# P_IN.net
KiCad netlist of a schematic drawn in Altium Designer
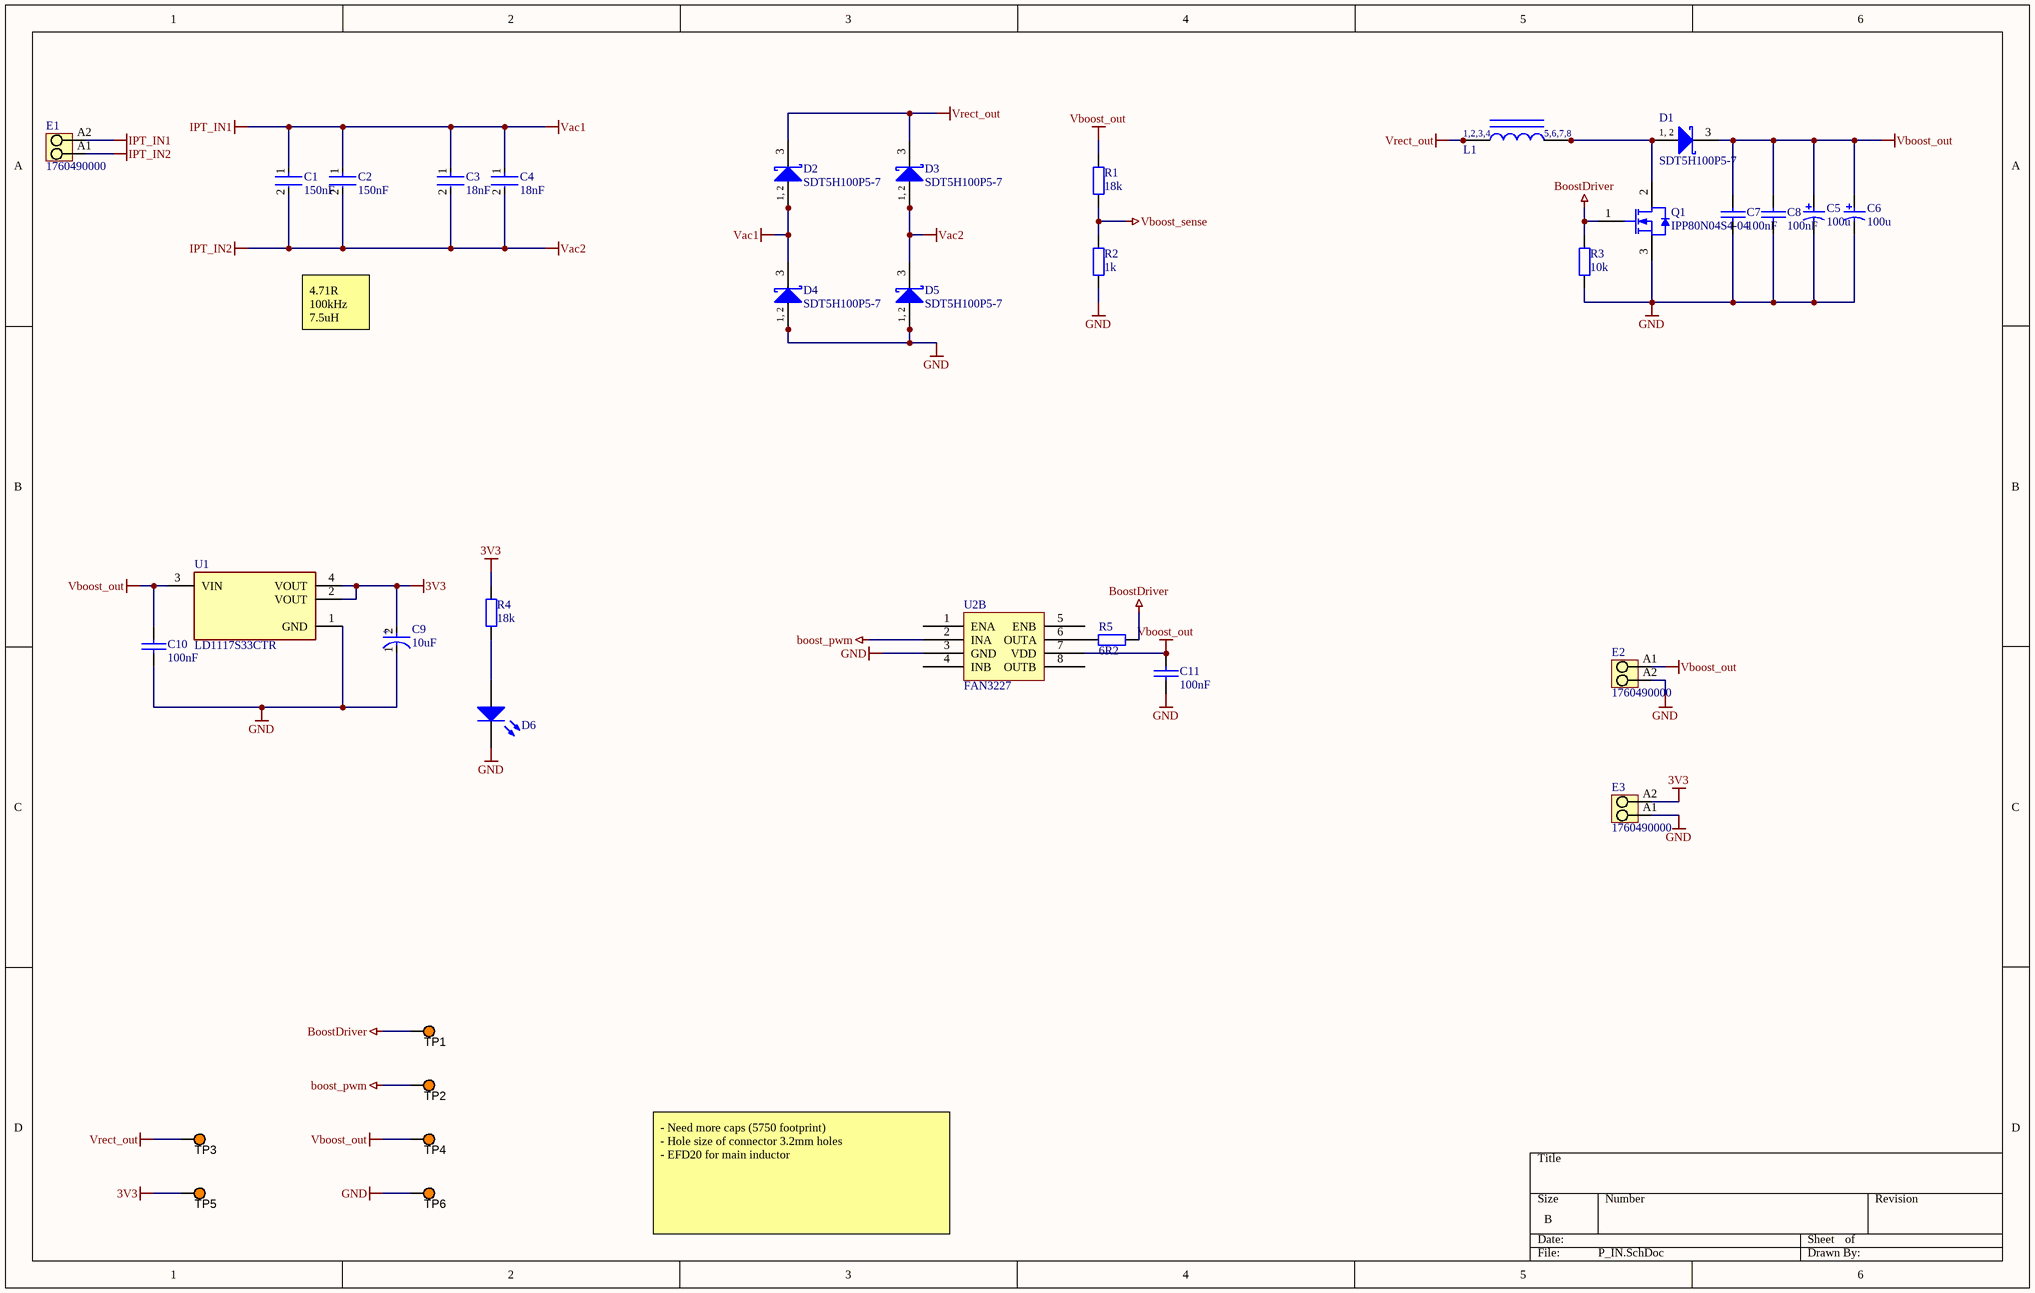
[diagram p0: P_IN.SchDoc]

(export (version "E")
  (design (tool "Eeschema 10.0.6"))
  (components
    (comp (ref "C1")
      (value "150nF")
      (footprint "FP-C5750-230-0_4-MFG")
      (description "Multilayer Ceramic Capacitors 10uF ±10% 50V X5R SMD 2220")
      (fields (field (name "TOLERANCE") "10%") (field (name "VOLTAGE") "50V"))
      (libsource (lib "Altium Content Vault") (part "02cd4be3c70576c341d710602a673aa"))
    )
    (comp (ref "C2")
      (value "150nF")
      (footprint "FP-C5750-230-0_4-MFG")
      (description "Multilayer Ceramic Capacitors 10uF ±10% 50V X5R SMD 2220")
      (fields (field (name "TOLERANCE") "10%") (field (name "VOLTAGE") "50V"))
      (libsource (lib "Altium Content Vault") (part "02cd4be3c70576c341d710602a673aa"))
    )
    (comp (ref "C3")
      (value "18nF")
      (footprint "FP-C5750-230-0_4-MFG")
      (description "Multilayer Ceramic Capacitors 10uF ±10% 50V X5R SMD 2220")
      (fields (field (name "TOLERANCE") "10%") (field (name "VOLTAGE") "50V"))
      (libsource (lib "Altium Content Vault") (part "02cd4be3c70576c341d710602a673aa"))
    )
    (comp (ref "C4")
      (value "18nF")
      (footprint "FP-C5750-230-0_4-MFG")
      (description "Multilayer Ceramic Capacitors 10uF ±10% 50V X5R SMD 2220")
      (fields (field (name "TOLERANCE") "10%") (field (name "VOLTAGE") "50V"))
      (libsource (lib "Altium Content Vault") (part "02cd4be3c70576c341d710602a673aa"))
    )
    (comp (ref "C5")
      (value "100u")
      (footprint "CAPAE7067X55L")
      (fields (field (name "MANUFACTURER") "Nichicon"))
      (libsource (lib "Altium Content Vault") (part "CAP-P-2"))
    )
    (comp (ref "C6")
      (value "100u")
      (footprint "CAPAE7067X55L")
      (fields (field (name "MANUFACTURER") "Nichicon"))
      (libsource (lib "Altium Content Vault") (part "CAP-P-2"))
    )
    (comp (ref "C7")
      (value "100nF")
      (footprint "0805 CAP")
      (description "SMT ceramic capacitor 0805 size")
      (libsource (lib "EE209_SchLib") (part "CerCap_SMT_0805"))
    )
    (comp (ref "C8")
      (value "100nF")
      (footprint "0805 CAP")
      (description "SMT ceramic capacitor 0805 size")
      (libsource (lib "EE209_SchLib") (part "CerCap_SMT_0805"))
    )
    (comp (ref "C9")
      (value "10uF")
      (footprint "FP-SB-MFG")
      (description "CAP ALUM 1UF 20% 50V SMD")
      (fields (field (name "TOLERANCE") "20%") (field (name "VOLTAGE") "50V"))
      (libsource (lib "Altium Content Vault") (part "203bc49f2ac43e59fd269a8c329ed05"))
    )
    (comp (ref "C10")
      (value "100nF")
      (footprint "0805 CAP")
      (description "SMT ceramic capacitor 0805 size")
      (libsource (lib "EE209_SchLib") (part "CerCap_SMT_0805"))
    )
    (comp (ref "C11")
      (value "100nF")
      (footprint "0805 CAP")
      (description "SMT ceramic capacitor 0805 size")
      (libsource (lib "EE209_SchLib") (part "CerCap_SMT_0805"))
    )
    (comp (ref "D1")
      (value "SDT5H100P5-7")
      (footprint "DIOD-POWERDI5-3_V")
      (description "Schottky Barrier Rectifier, 60 V, 7 A, -65 to 150 degC, 3-Pin SMD, RoHS, Tape and Reel")
      (fields (field (name "MANUFACTURER") "Diodes Inc"))
      (libsource (lib "Altium Content Vault") (part "DSKY-AAK-3_A"))
    )
    (comp (ref "D2")
      (value "SDT5H100P5-7")
      (footprint "DIOD-POWERDI5-3_V")
      (description "Schottky Barrier Rectifier, 60 V, 7 A, -65 to 150 degC, 3-Pin SMD, RoHS, Tape and Reel")
      (fields (field (name "MANUFACTURER") "Diodes Inc"))
      (libsource (lib "Altium Content Vault") (part "DSKY-AAK-3_A"))
    )
    (comp (ref "D3")
      (value "SDT5H100P5-7")
      (footprint "DIOD-POWERDI5-3_V")
      (description "Schottky Barrier Rectifier, 60 V, 7 A, -65 to 150 degC, 3-Pin SMD, RoHS, Tape and Reel")
      (fields (field (name "MANUFACTURER") "Diodes Inc"))
      (libsource (lib "Altium Content Vault") (part "DSKY-AAK-3_A"))
    )
    (comp (ref "D4")
      (value "SDT5H100P5-7")
      (footprint "DIOD-POWERDI5-3_V")
      (description "Schottky Barrier Rectifier, 60 V, 7 A, -65 to 150 degC, 3-Pin SMD, RoHS, Tape and Reel")
      (fields (field (name "MANUFACTURER") "Diodes Inc"))
      (libsource (lib "Altium Content Vault") (part "DSKY-AAK-3_A"))
    )
    (comp (ref "D5")
      (value "SDT5H100P5-7")
      (footprint "DIOD-POWERDI5-3_V")
      (description "Schottky Barrier Rectifier, 60 V, 7 A, -65 to 150 degC, 3-Pin SMD, RoHS, Tape and Reel")
      (fields (field (name "MANUFACTURER") "Diodes Inc"))
      (libsource (lib "Altium Content Vault") (part "DSKY-AAK-3_A"))
    )
    (comp (ref "D6")
      (value "LTST-C170KGKT")
      (footprint "0805 LED")
      (description "SMT LED 0805 size")
      (fields (field (name "MANUFACTURER") "Lite-On Inc."))
      (libsource (lib "EE209_Library") (part "LED_SMT_0805"))
    )
    (comp (ref "E1")
      (value "1760490000")
      (footprint "PM_5_08_90_02")
      (description "OMNIMATE Signal - series PM")
      (fields (field (name "MANUFACTURER") "Weidmueller"))
      (libsource (lib "Altium Content Vault") (part "Terminal_02_1x02"))
    )
    (comp (ref "E2")
      (value "1760490000")
      (footprint "PM_5_08_90_02")
      (description "OMNIMATE Signal - series PM")
      (fields (field (name "MANUFACTURER") "Weidmueller"))
      (libsource (lib "") (part "Terminal_02_1x02_1"))
    )
    (comp (ref "E3")
      (value "1760490000")
      (footprint "PM_5_08_90_02")
      (description "OMNIMATE Signal - series PM")
      (fields (field (name "MANUFACTURER") "Weidmueller"))
      (libsource (lib "Altium Content Vault") (part "Terminal_02_1x02"))
    )
    (comp (ref "L1")
      (value "Inductor")
      (footprint "EFD20")
      (description "Inductor with core")
      (libsource (lib "CommonDevices_V1") (part "Inductor EFD20"))
    )
    (comp (ref "Q1")
      (value "IPP80N04S4-04")
      (footprint "INF-PG-TO220-3-1")
      (description "OptiMOS-T2 Power-Transistor, 40 V VDS, 80 A ID, PG-TO220-3-1, Tube, Green")
      (fields (field (name "MANUFACTURER") "Infineon"))
      (libsource (lib "Altium Content Vault") (part "INF-MOSFET-N-3"))
    )
    (comp (ref "R1")
      (value "18k")
      (footprint "0805 RES")
      (description "0805 resistor")
      (fields (field (name "PUBLISHER") "Altium Limited"))
      (libsource (lib "EE209_SchLib") (part "Res_SMT_0805"))
    )
    (comp (ref "R2")
      (value "1k")
      (footprint "0805 RES")
      (description "0805 resistor")
      (fields (field (name "PUBLISHER") "Altium Limited"))
      (libsource (lib "EE209_SchLib") (part "Res_SMT_0805"))
    )
    (comp (ref "R3")
      (value "10k")
      (footprint "0805 RES")
      (description "0805 resistor")
      (fields (field (name "PUBLISHER") "Altium Limited"))
      (libsource (lib "EE209_SchLib") (part "Res_SMT_0805"))
    )
    (comp (ref "R4")
      (value "18k")
      (footprint "0805 RES")
      (description "0805 resistor")
      (fields (field (name "PUBLISHER") "Altium Limited"))
      (libsource (lib "EE209_SchLib") (part "Res_SMT_0805"))
    )
    (comp (ref "R5")
      (value "6R2")
      (footprint "0805 RES")
      (description "0805 resistor")
      (fields (field (name "PUBLISHER") "Altium Limited"))
      (libsource (lib "") (part "Res_SMT_0805_1"))
    )
    (comp (ref "TP1")
      (value "5003")
      (footprint "TP_TH")
      (description "Test Point, Orange, 1-Pin THD, RoHS")
      (libsource (lib "EE209_Library") (part "TestPoint"))
    )
    (comp (ref "TP2")
      (value "5003")
      (footprint "TP_TH")
      (description "Test Point, Orange, 1-Pin THD, RoHS")
      (libsource (lib "EE209_Library") (part "TestPoint"))
    )
    (comp (ref "TP3")
      (value "5003")
      (footprint "TP_TH")
      (description "Test Point, Orange, 1-Pin THD, RoHS")
      (libsource (lib "EE209_Library") (part "TestPoint"))
    )
    (comp (ref "TP4")
      (value "5003")
      (footprint "TP_TH")
      (description "Test Point, Orange, 1-Pin THD, RoHS")
      (libsource (lib "EE209_Library") (part "TestPoint"))
    )
    (comp (ref "TP5")
      (value "5003")
      (footprint "TP_TH")
      (description "Test Point, Orange, 1-Pin THD, RoHS")
      (libsource (lib "EE209_Library") (part "TestPoint"))
    )
    (comp (ref "TP6")
      (value "5003")
      (footprint "TP_TH")
      (description "Test Point, Orange, 1-Pin THD, RoHS")
      (libsource (lib "EE209_Library") (part "TestPoint"))
    )
    (comp (ref "U1")
      (value "LD1117S33CTR")
      (footprint "FP-SOT-223-0046067_14-MFG")
      (description "IC REG LINEAR 3.3V 800MA SOT223")
      (libsource (lib "Altium Content Vault") (part "7818869c5c16ceab15634627166a29d"))
    )
    (comp (ref "U2") (value "FAN3227") (footprint "SOIC-8") (libsource (lib "Schlib1") (part "FAN3227")))
  )
  (nets
    (net (code "1") (name "3V3") (class "Default")
      (node (ref "C9") (pin "2") (pinfunction "A_2") (pintype "passive"))
      (node (ref "E3") (pin "A2") (pinfunction "A2_A2") (pintype "passive"))
      (node (ref "R4") (pin "2") (pinfunction "2_2") (pintype "passive"))
      (node (ref "TP5") (pin "1") (pinfunction "1_1") (pintype "passive"))
      (node (ref "U1") (pin "2") (pinfunction "VOUT_2") (pintype "power_in"))
      (node (ref "U1") (pin "4") (pinfunction "VOUT_4") (pintype "power_in"))
    )
    (net (code "2") (name "BoostDriver") (class "Default")
      (node (ref "Q1") (pin "1") (pinfunction "GATE_1") (pintype "passive"))
      (node (ref "R3") (pin "2") (pinfunction "2_2") (pintype "passive"))
      (node (ref "R5") (pin "2") (pinfunction "2_2") (pintype "passive"))
      (node (ref "TP1") (pin "1") (pinfunction "1_1") (pintype "passive"))
    )
    (net (code "3") (name "GND") (class "Default")
      (node (ref "C10") (pin "2") (pinfunction "2_2") (pintype "passive"))
      (node (ref "C11") (pin "2") (pinfunction "2_2") (pintype "passive"))
      (node (ref "C5") (pin "2") (pinfunction "2_2") (pintype "passive"))
      (node (ref "C6") (pin "2") (pinfunction "2_2") (pintype "passive"))
      (node (ref "C7") (pin "2") (pinfunction "2_2") (pintype "passive"))
      (node (ref "C8") (pin "2") (pinfunction "2_2") (pintype "passive"))
      (node (ref "C9") (pin "1") (pinfunction "C_1") (pintype "passive"))
      (node (ref "D4") (pin "1") (pinfunction "A_1") (pintype "passive"))
      (node (ref "D4") (pin "2") (pinfunction "A_2") (pintype "passive"))
      (node (ref "D5") (pin "1") (pinfunction "A_1") (pintype "passive"))
      (node (ref "D5") (pin "2") (pinfunction "A_2") (pintype "passive"))
      (node (ref "D6") (pin "2") (pinfunction "K_2") (pintype "passive"))
      (node (ref "E2") (pin "A2") (pinfunction "A2_A2") (pintype "passive"))
      (node (ref "E3") (pin "A1") (pinfunction "A1_A1") (pintype "passive"))
      (node (ref "Q1") (pin "3") (pinfunction "SOURCE_3") (pintype "passive"))
      (node (ref "R2") (pin "1") (pinfunction "1_1") (pintype "passive"))
      (node (ref "R3") (pin "1") (pinfunction "1_1") (pintype "passive"))
      (node (ref "TP6") (pin "1") (pinfunction "1_1") (pintype "passive"))
      (node (ref "U1") (pin "1") (pinfunction "GND_1") (pintype "power_in"))
      (node (ref "U2") (pin "3") (pinfunction "GND_3") (pintype "passive"))
    )
    (net (code "4") (name "IPT_IN1") (class "Default")
      (node (ref "C1") (pin "1") (pinfunction "1_1") (pintype "passive"))
      (node (ref "C2") (pin "1") (pinfunction "1_1") (pintype "passive"))
      (node (ref "C3") (pin "1") (pinfunction "1_1") (pintype "passive"))
      (node (ref "C4") (pin "1") (pinfunction "1_1") (pintype "passive"))
      (node (ref "D2") (pin "1") (pinfunction "A_1") (pintype "passive"))
      (node (ref "D2") (pin "2") (pinfunction "A_2") (pintype "passive"))
      (node (ref "D4") (pin "3") (pinfunction "K_3") (pintype "passive"))
      (node (ref "E1") (pin "A2") (pinfunction "A2_A2") (pintype "passive"))
    )
    (net (code "5") (name "IPT_IN2") (class "Default")
      (node (ref "C1") (pin "2") (pinfunction "2_2") (pintype "passive"))
      (node (ref "C2") (pin "2") (pinfunction "2_2") (pintype "passive"))
      (node (ref "C3") (pin "2") (pinfunction "2_2") (pintype "passive"))
      (node (ref "C4") (pin "2") (pinfunction "2_2") (pintype "passive"))
      (node (ref "D3") (pin "1") (pinfunction "A_1") (pintype "passive"))
      (node (ref "D3") (pin "2") (pinfunction "A_2") (pintype "passive"))
      (node (ref "D5") (pin "3") (pinfunction "K_3") (pintype "passive"))
      (node (ref "E1") (pin "A1") (pinfunction "A1_A1") (pintype "passive"))
    )
    (net (code "6") (name "Net-(D6-A)") (class "Default")
      (node (ref "D6") (pin "1") (pinfunction "A_1") (pintype "passive"))
      (node (ref "R4") (pin "1") (pinfunction "1_1") (pintype "passive"))
    )
    (net (code "7") (name "Net-(Q1-DRAIN)") (class "Default")
      (node (ref "D1") (pin "1") (pinfunction "A_1") (pintype "passive"))
      (node (ref "D1") (pin "2") (pinfunction "A_2") (pintype "passive"))
      (node (ref "L1") (pin "5") (pinfunction "5_5") (pintype "passive"))
      (node (ref "L1") (pin "6") (pinfunction "6_6") (pintype "passive"))
      (node (ref "L1") (pin "7") (pinfunction "7_7") (pintype "passive"))
      (node (ref "L1") (pin "8") (pinfunction "8_8") (pintype "passive"))
      (node (ref "Q1") (pin "2") (pinfunction "DRAIN_2") (pintype "passive"))
    )
    (net (code "8") (name "Net-(U2B-OUTA)") (class "Default")
      (node (ref "R5") (pin "1") (pinfunction "1_1") (pintype "passive"))
      (node (ref "U2") (pin "6") (pinfunction "OUTA_6") (pintype "passive"))
    )
    (net (code "9") (name "Vboost_out") (class "Default")
      (node (ref "C10") (pin "1") (pinfunction "1_1") (pintype "passive"))
      (node (ref "C11") (pin "1") (pinfunction "1_1") (pintype "passive"))
      (node (ref "C5") (pin "1") (pinfunction "1_1") (pintype "passive"))
      (node (ref "C6") (pin "1") (pinfunction "1_1") (pintype "passive"))
      (node (ref "C7") (pin "1") (pinfunction "1_1") (pintype "passive"))
      (node (ref "C8") (pin "1") (pinfunction "1_1") (pintype "passive"))
      (node (ref "D1") (pin "3") (pinfunction "K_3") (pintype "passive"))
      (node (ref "E2") (pin "A1") (pinfunction "A1_A1") (pintype "passive"))
      (node (ref "R1") (pin "2") (pinfunction "2_2") (pintype "passive"))
      (node (ref "TP4") (pin "1") (pinfunction "1_1") (pintype "passive"))
      (node (ref "U1") (pin "3") (pinfunction "VIN_3") (pintype "power_in"))
      (node (ref "U2") (pin "7") (pinfunction "VDD_7") (pintype "passive"))
    )
    (net (code "10") (name "Vboost_sense") (class "Default")
      (node (ref "R1") (pin "1") (pinfunction "1_1") (pintype "passive"))
      (node (ref "R2") (pin "2") (pinfunction "2_2") (pintype "passive"))
    )
    (net (code "11") (name "Vrect_out") (class "Default")
      (node (ref "D2") (pin "3") (pinfunction "K_3") (pintype "passive"))
      (node (ref "D3") (pin "3") (pinfunction "K_3") (pintype "passive"))
      (node (ref "L1") (pin "1") (pinfunction "1_1") (pintype "passive"))
      (node (ref "L1") (pin "2") (pinfunction "2_2") (pintype "passive"))
      (node (ref "L1") (pin "3") (pinfunction "3_3") (pintype "passive"))
      (node (ref "L1") (pin "4") (pinfunction "4_4") (pintype "passive"))
      (node (ref "TP3") (pin "1") (pinfunction "1_1") (pintype "passive"))
    )
    (net (code "12") (name "boost_pwm") (class "Default")
      (node (ref "TP2") (pin "1") (pinfunction "1_1") (pintype "passive"))
      (node (ref "U2") (pin "2") (pinfunction "INA_2") (pintype "passive"))
    )
    (net (code "13") (name "unconnected-(U2B-ENA-Pad1)") (class "Default")
      (node (ref "U2") (pin "1") (pinfunction "ENA_1") (pintype "passive"))
    )
    (net (code "14") (name "unconnected-(U2B-ENB-Pad5)") (class "Default")
      (node (ref "U2") (pin "5") (pinfunction "ENB_5") (pintype "passive"))
    )
    (net (code "15") (name "unconnected-(U2B-INB-Pad4)") (class "Default")
      (node (ref "U2") (pin "4") (pinfunction "INB_4") (pintype "passive"))
    )
    (net (code "16") (name "unconnected-(U2B-OUTB-Pad8)") (class "Default")
      (node (ref "U2") (pin "8") (pinfunction "OUTB_8") (pintype "passive"))
    )
  )
)
